# POE.net
KiCad netlist of a schematic drawn in EAGLE
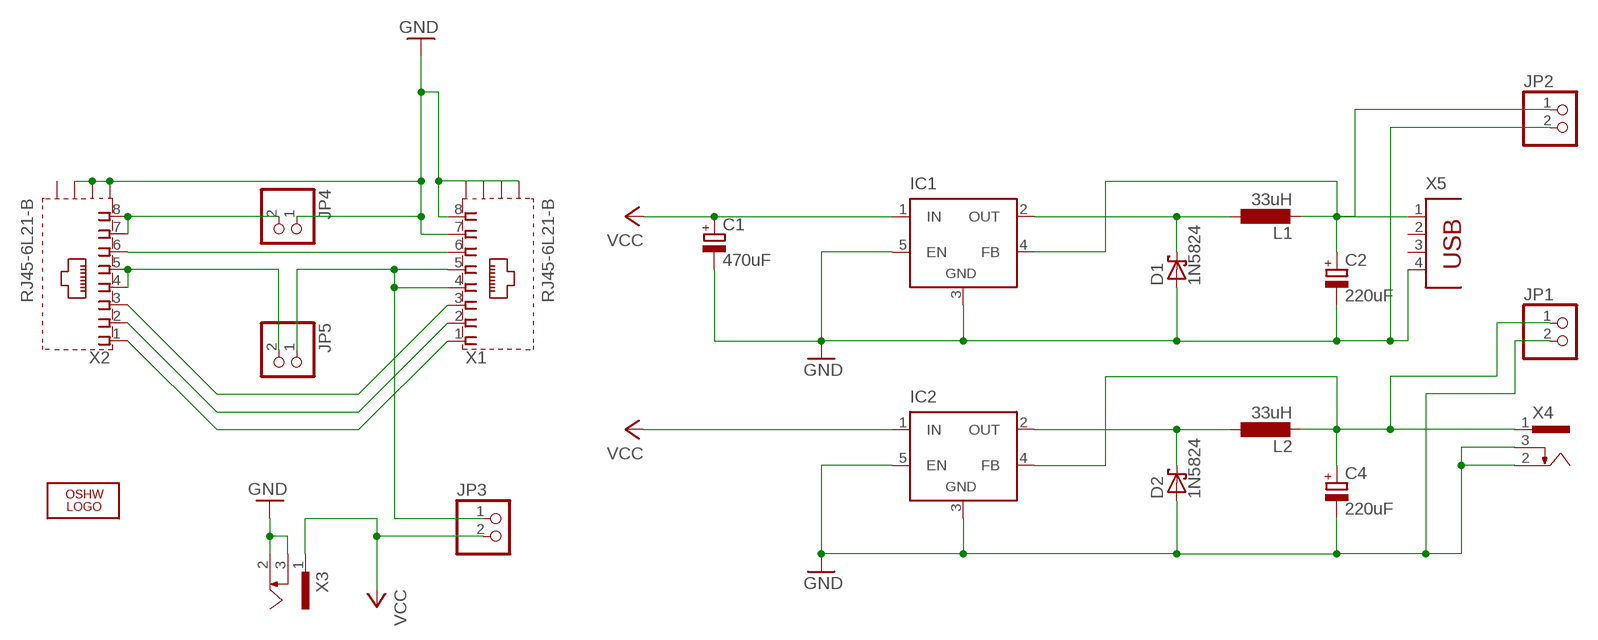
[diagram p0: schematic, sheet 1]

(export (version "E")
  (design (tool "Eeschema 10.0.6"))
  (components
    (comp (ref "C1")
      (value "470uF")
      (footprint "eagle-import:E3,5-8")
      (libsource (lib "eagle-import") (part "CPOL-EUE3.5-8"))
    )
    (comp (ref "C2")
      (value "220uF")
      (footprint "eagle-import:E2,5-7")
      (libsource (lib "eagle-import") (part "CPOL-EUE2.5-7"))
    )
    (comp (ref "C4")
      (value "220uF")
      (footprint "eagle-import:E2,5-7")
      (libsource (lib "eagle-import") (part "CPOL-EUE2.5-7"))
    )
    (comp (ref "D1")
      (value "1N5824")
      (footprint "eagle-import:DO35-10")
      (libsource (lib "eagle-import") (part "BAT19"))
    )
    (comp (ref "D2")
      (value "1N5824")
      (footprint "eagle-import:DO35-10")
      (libsource (lib "eagle-import") (part "BAT19"))
    )
    (comp (ref "IC1")
      (value "LM2596TV")
      (footprint "eagle-import:TO220-51")
      (libsource (lib "eagle-import") (part "LM2596TV"))
    )
    (comp (ref "IC2")
      (value "LM2596TV")
      (footprint "eagle-import:TO220-51")
      (libsource (lib "eagle-import") (part "LM2596TV"))
    )
    (comp (ref "JP1")
      (value "PINHD-1X2")
      (footprint "eagle-import:1X02")
      (libsource (lib "eagle-import") (part "PINHD-1X2"))
    )
    (comp (ref "JP2")
      (value "PINHD-1X2")
      (footprint "eagle-import:1X02")
      (libsource (lib "eagle-import") (part "PINHD-1X2"))
    )
    (comp (ref "JP3")
      (value "PINHD-1X2")
      (footprint "eagle-import:1X02")
      (libsource (lib "eagle-import") (part "PINHD-1X2"))
    )
    (comp (ref "JP4")
      (value "PINHD-1X2")
      (footprint "eagle-import:1X02")
      (libsource (lib "eagle-import") (part "PINHD-1X2"))
    )
    (comp (ref "JP5")
      (value "PINHD-1X2")
      (footprint "eagle-import:1X02")
      (libsource (lib "eagle-import") (part "PINHD-1X2"))
    )
    (comp (ref "L1")
      (value "33uH")
      (footprint "eagle-import:6000-XXXX-RC")
      (libsource (lib "eagle-import") (part "L-EU6000-XXX-RC"))
    )
    (comp (ref "L2")
      (value "33uH")
      (footprint "eagle-import:6000-XXXX-RC")
      (libsource (lib "eagle-import") (part "L-EU6000-XXX-RC"))
    )
    (comp (ref "LOGO1")
      (value "OSHW_LOGO_6MILX0200-NT")
      (footprint "eagle-import:OSHW_6X200_NOTEXT")
      (libsource (lib "eagle-import") (part "OSHW_LOGO_6MILX0200-NT"))
    )
    (comp (ref "X1")
      (value "RJ45-6L21-B")
      (footprint "eagle-import:RJ45-SHIELD1")
      (libsource (lib "eagle-import") (part "RJ4521-B-6L"))
    )
    (comp (ref "X2")
      (value "RJ45-6L21-B")
      (footprint "eagle-import:RJ45-SHIELD1")
      (libsource (lib "eagle-import") (part "RJ4521-B-6L"))
    )
    (comp (ref "X3")
      (value "733980-62")
      (footprint "eagle-import:733980-62")
      (libsource (lib "eagle-import") (part "73398?0-62"))
    )
    (comp (ref "X4")
      (value "733980-62")
      (footprint "eagle-import:733980-62")
      (libsource (lib "eagle-import") (part "73398?0-62"))
    )
    (comp (ref "X5")
      (value "PN87520")
      (footprint "eagle-import:PN87520")
      (libsource (lib "eagle-import") (part "PN87520"))
    )
  )
  (nets
    (net (code "1") (name "GND") (class "Default")
      (node (ref "C1") (pin "-") (pinfunction "-_-") (pintype "passive"))
      (node (ref "C2") (pin "-") (pinfunction "-_-") (pintype "passive"))
      (node (ref "C4") (pin "-") (pinfunction "-_-") (pintype "passive"))
      (node (ref "D1") (pin "A") (pinfunction "A_A") (pintype "passive"))
      (node (ref "D2") (pin "A") (pinfunction "A_A") (pintype "passive"))
      (node (ref "IC1") (pin "3") (pinfunction "GND_3") (pintype "power_in"))
      (node (ref "IC1") (pin "5") (pinfunction "EN_5") (pintype "input"))
      (node (ref "IC2") (pin "3") (pinfunction "GND_3") (pintype "power_in"))
      (node (ref "IC2") (pin "5") (pinfunction "EN_5") (pintype "input"))
      (node (ref "JP1") (pin "2") (pinfunction "2_2") (pintype "passive"))
      (node (ref "JP2") (pin "2") (pinfunction "2_2") (pintype "passive"))
      (node (ref "JP4") (pin "1") (pinfunction "1_1") (pintype "passive"))
      (node (ref "X1") (pin "7") (pinfunction "7_7") (pintype "passive"))
      (node (ref "X1") (pin "8") (pinfunction "8_8") (pintype "passive"))
      (node (ref "X1") (pin "S1") (pinfunction "S_S1") (pintype "passive"))
      (node (ref "X1") (pin "S2") (pinfunction "S_S2") (pintype "passive"))
      (node (ref "X1") (pin "S4") (pinfunction "S_S4") (pintype "passive"))
      (node (ref "X2") (pin "S1") (pinfunction "S_S1") (pintype "passive"))
      (node (ref "X2") (pin "S2") (pinfunction "S_S2") (pintype "passive"))
      (node (ref "X2") (pin "S3") (pinfunction "S_S3") (pintype "passive"))
      (node (ref "X3") (pin "2") (pinfunction "2_2") (pintype "passive"))
      (node (ref "X3") (pin "3") (pinfunction "3_3") (pintype "passive"))
      (node (ref "X4") (pin "2") (pinfunction "2_2") (pintype "passive"))
      (node (ref "X4") (pin "3") (pinfunction "3_3") (pintype "passive"))
      (node (ref "X5") (pin "4") (pinfunction "4_4") (pintype "passive"))
    )
    (net (code "2") (name "Net-(IC1-FB)") (class "Default")
      (node (ref "C2") (pin "+") (pinfunction "+_+") (pintype "passive"))
      (node (ref "IC1") (pin "4") (pinfunction "FB_4") (pintype "input"))
      (node (ref "JP2") (pin "1") (pinfunction "1_1") (pintype "passive"))
      (node (ref "L1") (pin "2") (pinfunction "2_2") (pintype "passive"))
      (node (ref "X5") (pin "1") (pinfunction "1_1") (pintype "passive"))
    )
    (net (code "3") (name "Net-(IC1-OUT)") (class "Default")
      (node (ref "D1") (pin "C") (pinfunction "C_C") (pintype "passive"))
      (node (ref "IC1") (pin "2") (pinfunction "OUT_2") (pintype "output"))
      (node (ref "L1") (pin "1") (pinfunction "1_1") (pintype "passive"))
    )
    (net (code "4") (name "Net-(IC2-FB)") (class "Default")
      (node (ref "C4") (pin "+") (pinfunction "+_+") (pintype "passive"))
      (node (ref "IC2") (pin "4") (pinfunction "FB_4") (pintype "input"))
      (node (ref "JP1") (pin "1") (pinfunction "1_1") (pintype "passive"))
      (node (ref "L2") (pin "2") (pinfunction "2_2") (pintype "passive"))
      (node (ref "X4") (pin "1") (pinfunction "1_1") (pintype "passive"))
    )
    (net (code "5") (name "Net-(IC2-OUT)") (class "Default")
      (node (ref "D2") (pin "C") (pinfunction "C_C") (pintype "passive"))
      (node (ref "IC2") (pin "2") (pinfunction "OUT_2") (pintype "output"))
      (node (ref "L2") (pin "1") (pinfunction "1_1") (pintype "passive"))
    )
    (net (code "6") (name "Net-(JP3-Pad1)") (class "Default")
      (node (ref "JP3") (pin "1") (pinfunction "1_1") (pintype "passive"))
      (node (ref "JP5") (pin "1") (pinfunction "1_1") (pintype "passive"))
      (node (ref "X1") (pin "4") (pinfunction "4_4") (pintype "passive"))
      (node (ref "X1") (pin "5") (pinfunction "5_5") (pintype "passive"))
    )
    (net (code "7") (name "Net-(JP4-Pad2)") (class "Default")
      (node (ref "JP4") (pin "2") (pinfunction "2_2") (pintype "passive"))
      (node (ref "X2") (pin "7") (pinfunction "7_7") (pintype "passive"))
      (node (ref "X2") (pin "8") (pinfunction "8_8") (pintype "passive"))
    )
    (net (code "8") (name "Net-(JP5-Pad2)") (class "Default")
      (node (ref "JP5") (pin "2") (pinfunction "2_2") (pintype "passive"))
      (node (ref "X2") (pin "4") (pinfunction "4_4") (pintype "passive"))
      (node (ref "X2") (pin "5") (pinfunction "5_5") (pintype "passive"))
    )
    (net (code "9") (name "Net-(X1-Pad1)") (class "Default")
      (node (ref "X1") (pin "1") (pinfunction "1_1") (pintype "passive"))
      (node (ref "X2") (pin "1") (pinfunction "1_1") (pintype "passive"))
    )
    (net (code "10") (name "Net-(X1-Pad2)") (class "Default")
      (node (ref "X1") (pin "2") (pinfunction "2_2") (pintype "passive"))
      (node (ref "X2") (pin "2") (pinfunction "2_2") (pintype "passive"))
    )
    (net (code "11") (name "Net-(X1-Pad3)") (class "Default")
      (node (ref "X1") (pin "3") (pinfunction "3_3") (pintype "passive"))
      (node (ref "X2") (pin "3") (pinfunction "3_3") (pintype "passive"))
    )
    (net (code "12") (name "Net-(X1-Pad6)") (class "Default")
      (node (ref "X1") (pin "6") (pinfunction "6_6") (pintype "passive"))
      (node (ref "X2") (pin "6") (pinfunction "6_6") (pintype "passive"))
    )
    (net (code "13") (name "VCC") (class "Default")
      (node (ref "C1") (pin "+") (pinfunction "+_+") (pintype "passive"))
      (node (ref "IC1") (pin "1") (pinfunction "IN_1") (pintype "input"))
      (node (ref "IC2") (pin "1") (pinfunction "IN_1") (pintype "input"))
      (node (ref "JP3") (pin "2") (pinfunction "2_2") (pintype "passive"))
      (node (ref "X3") (pin "1") (pinfunction "1_1") (pintype "passive"))
    )
    (net (code "14") (name "unconnected-(X1-S-PadS3)") (class "Default")
      (node (ref "X1") (pin "S3") (pinfunction "S_S3") (pintype "passive"))
    )
    (net (code "15") (name "unconnected-(X2-S-PadS4)") (class "Default")
      (node (ref "X2") (pin "S4") (pinfunction "S_S4") (pintype "passive"))
    )
    (net (code "16") (name "unconnected-(X5-Pad2)") (class "Default")
      (node (ref "X5") (pin "2") (pinfunction "2_2") (pintype "passive"))
    )
    (net (code "17") (name "unconnected-(X5-Pad3)") (class "Default")
      (node (ref "X5") (pin "3") (pinfunction "3_3") (pintype "passive"))
    )
  )
)
